# final_version_1.net
KiCad netlist of a schematic drawn in EAGLE
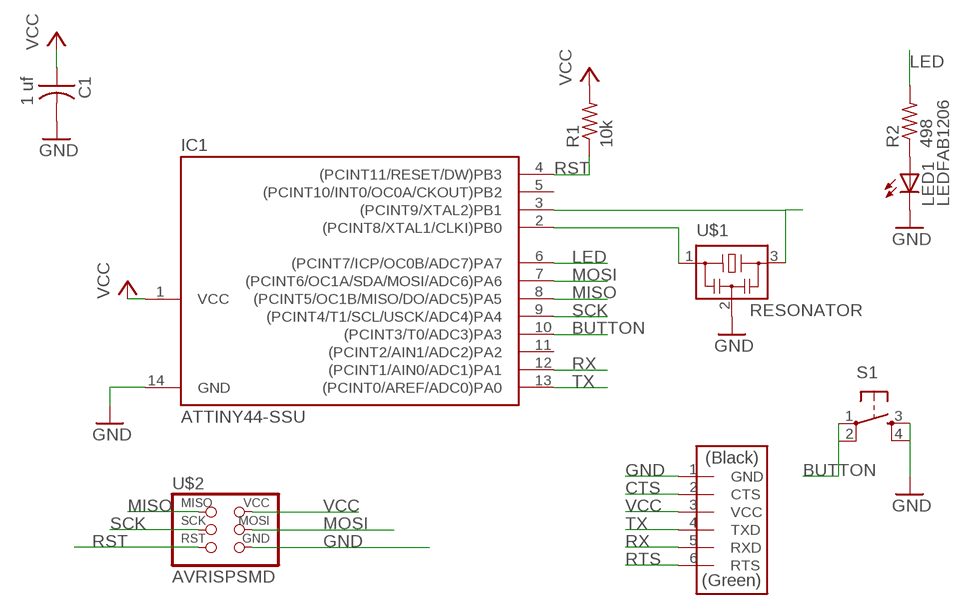
[diagram p0: schematic, sheet 1]

(export (version "E")
  (design (tool "Eeschema 10.0.6"))
  (components
    (comp (ref "C1")
      (value "1 uf")
      (footprint "eagle-import:C1206FAB")
      (libsource (lib "eagle-import") (part "CAP-US1206FAB"))
    )
    (comp (ref "IC1")
      (value "ATTINY44-SSU")
      (footprint "eagle-import:SOIC14")
      (libsource (lib "eagle-import") (part "ATTINY44-SSU"))
    )
    (comp (ref "LED1")
      (value "LEDFAB1206")
      (footprint "eagle-import:LED1206FAB")
      (libsource (lib "eagle-import") (part "LEDFAB1206"))
    )
    (comp (ref "R1")
      (value "10k")
      (footprint "eagle-import:R1206FAB")
      (libsource (lib "eagle-import") (part "RES-US1206FAB"))
    )
    (comp (ref "R2")
      (value "498")
      (footprint "eagle-import:R1206FAB")
      (libsource (lib "eagle-import") (part "RES-US1206FAB"))
    )
    (comp (ref "S1")
      (value "6MM_SWITCH6MM_SWITCH")
      (footprint "eagle-import:6MM_SWITCH")
      (libsource (lib "eagle-import") (part "6MM_SWITCH6MM_SWITCH"))
    )
    (comp (ref "U$1")
      (value "RESONATOR")
      (footprint "eagle-import:EFOBM")
      (libsource (lib "eagle-import") (part "RESONATOR"))
    )
    (comp (ref "U$2")
      (value "AVRISPSMD")
      (footprint "eagle-import:2X03SMD")
      (libsource (lib "eagle-import") (part "AVRISPSMD"))
    )
    (comp (ref "U$3")
      (value "FTDI-SMD-HEADER")
      (footprint "eagle-import:1X06SMD")
      (libsource (lib "eagle-import") (part "FTDI-SMD-HEADER"))
    )
  )
  (nets
    (net (code "1") (name "/BUTTON") (class "Default")
      (node (ref "IC1") (pin "10") (pinfunction "(PCINT3/T0/ADC3)PA3_10") (pintype "bidirectional"))
      (node (ref "S1") (pin "1") (pinfunction "P_1") (pintype "passive"))
    )
    (net (code "2") (name "/CTS") (class "Default")
      (node (ref "U$3") (pin "2") (pinfunction "CTS_2") (pintype "bidirectional"))
    )
    (net (code "3") (name "/LED") (class "Default")
      (node (ref "IC1") (pin "6") (pinfunction "(PCINT7/ICP/OC0B/ADC7)PA7_6") (pintype "bidirectional"))
      (node (ref "R2") (pin "2") (pinfunction "2_2") (pintype "passive"))
    )
    (net (code "4") (name "/MISO") (class "Default")
      (node (ref "IC1") (pin "8") (pinfunction "(PCINT5/OC1B/MISO/DO/ADC5)PA5_8") (pintype "bidirectional"))
      (node (ref "U$2") (pin "1") (pinfunction "MISO_1") (pintype "passive"))
    )
    (net (code "5") (name "/MOSI") (class "Default")
      (node (ref "IC1") (pin "7") (pinfunction "(PCINT6/OC1A/SDA/MOSI/ADC6)PA6_7") (pintype "bidirectional"))
      (node (ref "U$2") (pin "4") (pinfunction "MOSI_4") (pintype "passive"))
    )
    (net (code "6") (name "/RST") (class "Default")
      (node (ref "IC1") (pin "4") (pinfunction "(PCINT11/RESET/DW)PB3_4") (pintype "bidirectional"))
      (node (ref "R1") (pin "1") (pinfunction "1_1") (pintype "passive"))
      (node (ref "U$2") (pin "5") (pinfunction "RST_5") (pintype "passive"))
    )
    (net (code "7") (name "/RTS") (class "Default")
      (node (ref "U$3") (pin "6") (pinfunction "RTS_6") (pintype "bidirectional"))
    )
    (net (code "8") (name "/RX") (class "Default")
      (node (ref "IC1") (pin "12") (pinfunction "(PCINT1/AIN0/ADC1)PA1_12") (pintype "bidirectional"))
      (node (ref "U$3") (pin "5") (pinfunction "RXD_5") (pintype "bidirectional"))
    )
    (net (code "9") (name "/SCK") (class "Default")
      (node (ref "IC1") (pin "9") (pinfunction "(PCINT4/T1/SCL/USCK/ADC4)PA4_9") (pintype "bidirectional"))
      (node (ref "U$2") (pin "3") (pinfunction "SCK_3") (pintype "passive"))
    )
    (net (code "10") (name "/TX") (class "Default")
      (node (ref "IC1") (pin "13") (pinfunction "(PCINT0/AREF/ADC0)PA0_13") (pintype "bidirectional"))
      (node (ref "U$3") (pin "4") (pinfunction "TXD_4") (pintype "bidirectional"))
    )
    (net (code "11") (name "GND") (class "Default")
      (node (ref "C1") (pin "2") (pinfunction "2_2") (pintype "passive"))
      (node (ref "IC1") (pin "14") (pinfunction "GND_14") (pintype "power_in"))
      (node (ref "LED1") (pin "2") (pinfunction "C_2") (pintype "passive"))
      (node (ref "S1") (pin "3") (pinfunction "S_3") (pintype "passive"))
      (node (ref "U$1") (pin "2") (pinfunction "2_2") (pintype "passive"))
      (node (ref "U$2") (pin "6") (pinfunction "GND_6") (pintype "passive"))
      (node (ref "U$3") (pin "1") (pinfunction "GND_1") (pintype "bidirectional"))
    )
    (net (code "12") (name "Net-(IC1-(PCINT8{slash}XTAL1{slash}CLKI)PB0)") (class "Default")
      (node (ref "IC1") (pin "2") (pinfunction "(PCINT8/XTAL1/CLKI)PB0_2") (pintype "bidirectional"))
      (node (ref "U$1") (pin "1") (pinfunction "1_1") (pintype "passive"))
    )
    (net (code "13") (name "Net-(IC1-(PCINT9{slash}XTAL2)PB1)") (class "Default")
      (node (ref "IC1") (pin "3") (pinfunction "(PCINT9/XTAL2)PB1_3") (pintype "bidirectional"))
      (node (ref "U$1") (pin "3") (pinfunction "3_3") (pintype "passive"))
    )
    (net (code "14") (name "Net-(LED1-A)") (class "Default")
      (node (ref "LED1") (pin "1") (pinfunction "A_1") (pintype "passive"))
      (node (ref "R2") (pin "1") (pinfunction "1_1") (pintype "passive"))
    )
    (net (code "15") (name "VCC") (class "Default")
      (node (ref "C1") (pin "1") (pinfunction "1_1") (pintype "passive"))
      (node (ref "IC1") (pin "1") (pinfunction "VCC_1") (pintype "power_in"))
      (node (ref "R1") (pin "2") (pinfunction "2_2") (pintype "passive"))
      (node (ref "U$2") (pin "2") (pinfunction "VCC_2") (pintype "passive"))
      (node (ref "U$3") (pin "3") (pinfunction "VCC_3") (pintype "bidirectional"))
    )
    (net (code "16") (name "unconnected-(IC1-(PCINT2{slash}AIN1{slash}ADC2)PA2-Pad11)") (class "Default")
      (node (ref "IC1") (pin "11") (pinfunction "(PCINT2/AIN1/ADC2)PA2_11") (pintype "bidirectional"))
    )
    (net (code "17") (name "unconnected-(IC1-(PCINT10{slash}INT0{slash}OC0A{slash}CKOUT)PB2-Pad5)") (class "Default")
      (node (ref "IC1") (pin "5") (pinfunction "(PCINT10/INT0/OC0A/CKOUT)PB2_5") (pintype "bidirectional"))
    )
    (net (code "18") (name "unconnected-(S1-P1-Pad2)") (class "Default")
      (node (ref "S1") (pin "2") (pinfunction "P1_2") (pintype "passive"))
    )
    (net (code "19") (name "unconnected-(S1-S1-Pad4)") (class "Default")
      (node (ref "S1") (pin "4") (pinfunction "S1_4") (pintype "passive"))
    )
  )
)
